# curvetracer.net
KiCad netlist of a schematic drawn in EAGLE
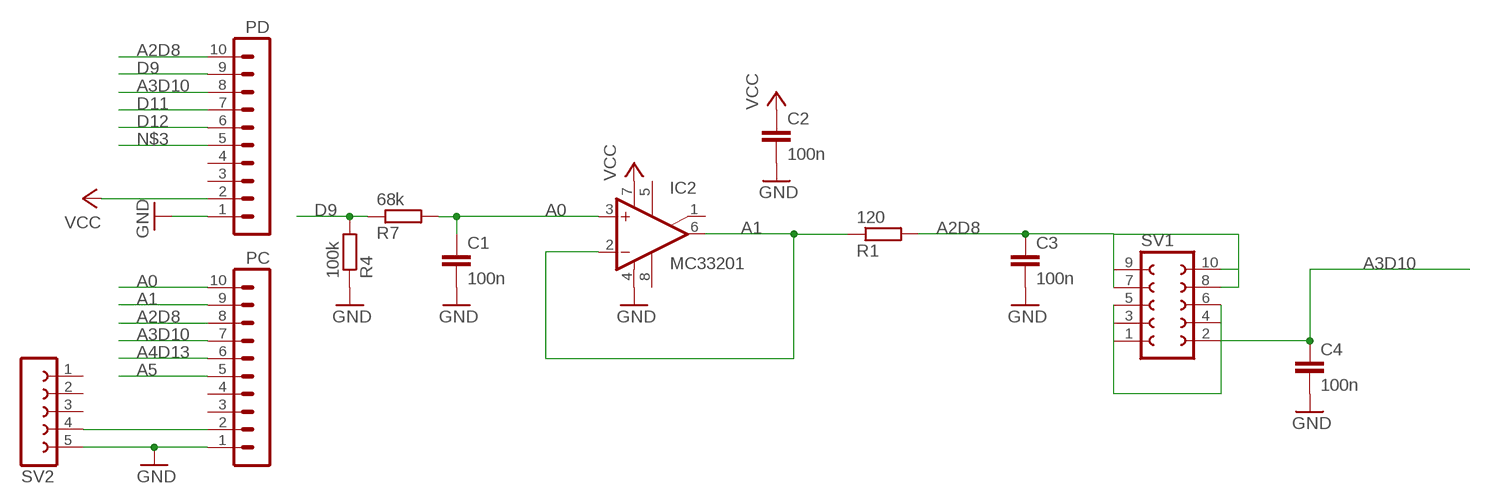
[diagram p0: schematic, sheet 1]

(export (version "E")
  (design (tool "Eeschema 10.0.6"))
  (components
    (comp (ref "C1")
      (value "100n")
      (footprint "eagle-import:C025-024X044")
      (libsource (lib "eagle-import") (part "C-EU025-024X044"))
    )
    (comp (ref "C2")
      (value "100n")
      (footprint "eagle-import:C025-024X044")
      (libsource (lib "eagle-import") (part "C-EU025-024X044"))
    )
    (comp (ref "C3")
      (value "100n")
      (footprint "eagle-import:C075-032X103")
      (libsource (lib "eagle-import") (part "C-EU075-032X103"))
    )
    (comp (ref "C4")
      (value "100n")
      (footprint "eagle-import:C102-043X133")
      (libsource (lib "eagle-import") (part "C-EU102-043X133"))
    )
    (comp (ref "IC2")
      (value "MC33201")
      (footprint "eagle-import:DIL08")
      (libsource (lib "eagle-import") (part "CA3130N"))
    )
    (comp (ref "PC")
      (value "MA10-1W")
      (footprint "eagle-import:MA10-1W")
      (libsource (lib "eagle-import") (part "MA10-1W"))
    )
    (comp (ref "PD")
      (value "MA10-1W")
      (footprint "eagle-import:MA10-1W")
      (libsource (lib "eagle-import") (part "MA10-1W"))
    )
    (comp (ref "R1")
      (value "120")
      (footprint "eagle-import:R1206")
      (libsource (lib "eagle-import") (part "R-EU_R1206"))
    )
    (comp (ref "R4")
      (value "100k")
      (footprint "eagle-import:R1206")
      (libsource (lib "eagle-import") (part "R-EU_R1206"))
    )
    (comp (ref "R7")
      (value "68k")
      (footprint "eagle-import:R1206")
      (libsource (lib "eagle-import") (part "R-EU_R1206"))
    )
    (comp (ref "SV1")
      (value "FE05-2W")
      (footprint "eagle-import:FE05-2W")
      (libsource (lib "eagle-import") (part "FE05-2W"))
    )
    (comp (ref "SV2")
      (value "FE05W")
      (footprint "eagle-import:FE05W")
      (libsource (lib "eagle-import") (part "FE05W"))
    )
  )
  (nets
    (net (code "1") (name "/A0") (class "Default")
      (node (ref "C1") (pin "1") (pinfunction "1_1") (pintype "passive"))
      (node (ref "IC2") (pin "3") (pinfunction "+IN_3") (pintype "input"))
      (node (ref "PC") (pin "10") (pinfunction "10_10") (pintype "passive"))
      (node (ref "R7") (pin "2") (pinfunction "2_2") (pintype "passive"))
    )
    (net (code "2") (name "/A1") (class "Default")
      (node (ref "IC2") (pin "2") (pinfunction "-IN_2") (pintype "input"))
      (node (ref "IC2") (pin "6") (pinfunction "OUT_6") (pintype "output"))
      (node (ref "PC") (pin "9") (pinfunction "9_9") (pintype "passive"))
      (node (ref "R1") (pin "1") (pinfunction "1_1") (pintype "passive"))
    )
    (net (code "3") (name "/A2D8") (class "Default")
      (node (ref "C3") (pin "1") (pinfunction "1_1") (pintype "passive"))
      (node (ref "PC") (pin "8") (pinfunction "8_8") (pintype "passive"))
      (node (ref "PD") (pin "10") (pinfunction "10_10") (pintype "passive"))
      (node (ref "R1") (pin "2") (pinfunction "2_2") (pintype "passive"))
      (node (ref "SV1") (pin "10") (pinfunction "10_10") (pintype "passive"))
      (node (ref "SV1") (pin "7") (pinfunction "7_7") (pintype "passive"))
      (node (ref "SV1") (pin "8") (pinfunction "8_8") (pintype "passive"))
      (node (ref "SV1") (pin "9") (pinfunction "9_9") (pintype "passive"))
    )
    (net (code "4") (name "/A3D10") (class "Default")
      (node (ref "C4") (pin "1") (pinfunction "1_1") (pintype "passive"))
      (node (ref "PC") (pin "7") (pinfunction "7_7") (pintype "passive"))
      (node (ref "PD") (pin "8") (pinfunction "8_8") (pintype "passive"))
      (node (ref "SV1") (pin "1") (pinfunction "1_1") (pintype "passive"))
      (node (ref "SV1") (pin "2") (pinfunction "2_2") (pintype "passive"))
      (node (ref "SV1") (pin "3") (pinfunction "3_3") (pintype "passive"))
      (node (ref "SV1") (pin "4") (pinfunction "4_4") (pintype "passive"))
      (node (ref "SV1") (pin "5") (pinfunction "5_5") (pintype "passive"))
      (node (ref "SV1") (pin "6") (pinfunction "6_6") (pintype "passive"))
    )
    (net (code "5") (name "/A4D13") (class "Default")
      (node (ref "PC") (pin "6") (pinfunction "6_6") (pintype "passive"))
    )
    (net (code "6") (name "/A5") (class "Default")
      (node (ref "PC") (pin "5") (pinfunction "5_5") (pintype "passive"))
    )
    (net (code "7") (name "/D9") (class "Default")
      (node (ref "PD") (pin "9") (pinfunction "9_9") (pintype "passive"))
      (node (ref "R4") (pin "2") (pinfunction "2_2") (pintype "passive"))
      (node (ref "R7") (pin "1") (pinfunction "1_1") (pintype "passive"))
    )
    (net (code "8") (name "/D11") (class "Default")
      (node (ref "PD") (pin "7") (pinfunction "7_7") (pintype "passive"))
    )
    (net (code "9") (name "/D12") (class "Default")
      (node (ref "PD") (pin "6") (pinfunction "6_6") (pintype "passive"))
    )
    (net (code "10") (name "/N$3") (class "Default")
      (node (ref "PD") (pin "5") (pinfunction "5_5") (pintype "passive"))
    )
    (net (code "11") (name "GND") (class "Default")
      (node (ref "C1") (pin "2") (pinfunction "2_2") (pintype "passive"))
      (node (ref "C2") (pin "2") (pinfunction "2_2") (pintype "passive"))
      (node (ref "C3") (pin "2") (pinfunction "2_2") (pintype "passive"))
      (node (ref "C4") (pin "2") (pinfunction "2_2") (pintype "passive"))
      (node (ref "IC2") (pin "4") (pinfunction "V-_4") (pintype "power_in"))
      (node (ref "PC") (pin "1") (pinfunction "1_1") (pintype "passive"))
      (node (ref "PD") (pin "1") (pinfunction "1_1") (pintype "passive"))
      (node (ref "R4") (pin "1") (pinfunction "1_1") (pintype "passive"))
      (node (ref "SV2") (pin "5") (pinfunction "5_5") (pintype "passive"))
    )
    (net (code "12") (name "Net-(PC-Pad2)") (class "Default")
      (node (ref "PC") (pin "2") (pinfunction "2_2") (pintype "passive"))
      (node (ref "SV2") (pin "4") (pinfunction "4_4") (pintype "passive"))
    )
    (net (code "13") (name "VCC") (class "Default")
      (node (ref "C2") (pin "1") (pinfunction "1_1") (pintype "passive"))
      (node (ref "IC2") (pin "7") (pinfunction "V+_7") (pintype "power_in"))
      (node (ref "PD") (pin "2") (pinfunction "2_2") (pintype "passive"))
    )
    (net (code "14") (name "unconnected-(IC2-CMP-Pad8)") (class "Default")
      (node (ref "IC2") (pin "8") (pinfunction "CMP_8") (pintype "passive"))
    )
    (net (code "15") (name "unconnected-(IC2-ON-Pad5)") (class "Default")
      (node (ref "IC2") (pin "5") (pinfunction "ON_5") (pintype "passive"))
    )
    (net (code "16") (name "unconnected-(IC2-ON{slash}CMP-Pad1)") (class "Default")
      (node (ref "IC2") (pin "1") (pinfunction "ON/CMP_1") (pintype "passive"))
    )
    (net (code "17") (name "unconnected-(PC-Pad3)") (class "Default")
      (node (ref "PC") (pin "3") (pinfunction "3_3") (pintype "passive"))
    )
    (net (code "18") (name "unconnected-(PC-Pad4)") (class "Default")
      (node (ref "PC") (pin "4") (pinfunction "4_4") (pintype "passive"))
    )
    (net (code "19") (name "unconnected-(PD-Pad3)") (class "Default")
      (node (ref "PD") (pin "3") (pinfunction "3_3") (pintype "passive"))
    )
    (net (code "20") (name "unconnected-(PD-Pad4)") (class "Default")
      (node (ref "PD") (pin "4") (pinfunction "4_4") (pintype "passive"))
    )
    (net (code "21") (name "unconnected-(SV2-Pad1)") (class "Default")
      (node (ref "SV2") (pin "1") (pinfunction "1_1") (pintype "passive"))
    )
    (net (code "22") (name "unconnected-(SV2-Pad2)") (class "Default")
      (node (ref "SV2") (pin "2") (pinfunction "2_2") (pintype "passive"))
    )
    (net (code "23") (name "unconnected-(SV2-Pad3)") (class "Default")
      (node (ref "SV2") (pin "3") (pinfunction "3_3") (pintype "passive"))
    )
  )
)
